# SH1-POWER.net
KiCad netlist of a schematic drawn in Altium Designer
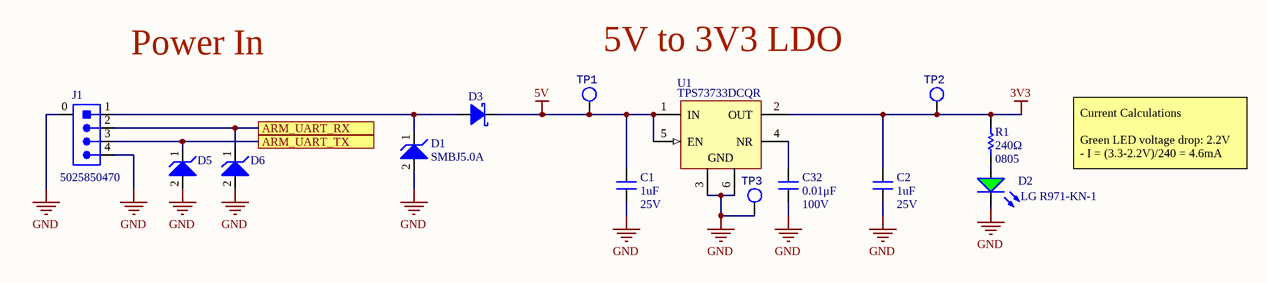
[diagram p0: SH1-POWER.SchDoc]

(export (version "E")
  (design (tool "Eeschema 10.0.6"))
  (components
    (comp (ref "C1")
      (value "~")
      (footprint "CAPC2012X140N")
      (description "CAP CER 1UF 25V X7R 0805")
      (fields
        (field (name "TOLERANCE") "10%")
        (field (name "CAPACITANCE") "1uF")
        (field (name "VOLTAGE RATING (DC)") "25V")
      )
      (libsource (lib "*") (part "CAP_1uF_25V_0805"))
    )
    (comp (ref "C2")
      (value "~")
      (footprint "CAPC2012X140N")
      (description "CAP CER 1UF 25V X7R 0805")
      (fields
        (field (name "TOLERANCE") "10%")
        (field (name "CAPACITANCE") "1uF")
        (field (name "VOLTAGE RATING (DC)") "25V")
      )
      (libsource (lib "*") (part "CAP_1uF_25V_0805"))
    )
    (comp (ref "C32")
      (value "0.01μF")
      (footprint "CAP2012")
      (description "CAP CER 10000PF 100V X7R 0805")
      (fields
        (field (name "TOLERANCE") "10%")
        (field (name "VOLTAGE RATING") "100V")
        (field (name "Comment") "CAP_0.01uF_100V_0805")
      )
      (libsource (lib "UWRT_Schematic_Library_2020") (part "CAP_0.01uF_100V_0805"))
    )
    (comp (ref "D1")
      (value "TVS_DIODE_UNIDIR_5V")
      (footprint "SMBJ5.0A")
      (description "TVS DIODE 5V 9.2V DO214AA")
      (fields (field (name "MANUFACTURER PART NUMBER 1") "SMBJ5.0A"))
      (libsource (lib "UWRT_Schematic_Library_2020") (part "TVS_DIODE_UNIDIR_5V"))
    )
    (comp (ref "D2")
      (value "LG R971-KN-1")
      (footprint "LED_0805_LINE")
      (description "LED GREEN DIFFUSED 0805 SMD")
      (libsource (lib "UWRT_Schematic_Library_2020") (part "DIO_LED_G"))
    )
    (comp (ref "D3")
      (value "DIO_SCHOTTKY_30V_2A")
      (footprint "SOD-128")
      (description "DIODE SCHOTTKY 30V 2A PMDTM")
      (libsource (lib "UWRT_Schematic_Library_2020") (part "DIO_SCHOTTKY_30V_2A"))
    )
    (comp (ref "D5")
      (value "TVS_DIODE_UNIDIR_3.3V")
      (footprint "SOD523")
      (description "TVS DIODE 3.3V 14.1V SOD523. Used to protect each connector input line going into the MCU.")
      (libsource (lib "UWRT_Schematic_Library_2020") (part "TVS_DIODE_UNIDIR_3.3V"))
    )
    (comp (ref "D6")
      (value "TVS_DIODE_UNIDIR_3.3V")
      (footprint "SOD523")
      (description "TVS DIODE 3.3V 14.1V SOD523. Used to protect each connector input line going into the MCU.")
      (libsource (lib "UWRT_Schematic_Library_2020") (part "TVS_DIODE_UNIDIR_3.3V"))
    )
    (comp (ref "J1")
      (value "CON_4M_SM_RA")
      (footprint "MOLEX-5025850470")
      (description "CONN HEADER SMD RIGHT ANGLE 1.5 MM PITCH")
      (fields (field (name "MANUFACTURER") "Molex") (field (name "MANUFACTOR NUMBER") "5025850470"))
      (libsource (lib "UWRT_Schematic_Library_2020") (part "CON_4M_SM_RA"))
    )
    (comp (ref "R1")
      (value "240")
      (footprint "RESC2012X60N")
      (description "RES 240 OHM 1% 1/8W 0805")
      (fields
        (field (name "TOLERANCE") "1%")
        (field (name "RESISTANCE") "240Ω")
        (field (name "CASE CODE (IMPERIAL)") "0805")
      )
      (libsource (lib "UWRT_Schematic_Library_2020") (part "RES_240Ω_0805_1%"))
    )
    (comp (ref "TP1")
      (value "TESTPOINT_LOOP")
      (footprint "TESTPOINT_LOOP")
      (description "Loop testpoint through-hole pad")
      (libsource (lib "UWRT_Schematic_Library_2020") (part "TESTPOINT_LOOP"))
    )
    (comp (ref "TP2")
      (value "TESTPOINT_LOOP")
      (footprint "TESTPOINT_LOOP")
      (description "Loop testpoint through-hole pad")
      (libsource (lib "UWRT_Schematic_Library_2020") (part "TESTPOINT_LOOP"))
    )
    (comp (ref "TP3")
      (value "TESTPOINT_LOOP")
      (footprint "TESTPOINT_LOOP")
      (description "Loop testpoint through-hole pad")
      (libsource (lib "UWRT_Schematic_Library_2020") (part "TESTPOINT_LOOP"))
    )
    (comp (ref "U1")
      (value "TPS73733DCQR")
      (footprint "UWRT_Footprint_Library_2020:SOT-223-6")
      (description "IC REG LINEAR 3.3V 1A SOT223-6")
      (fields (field (name "MANUFACTURER") "Texas Instruments"))
      (libsource (lib "Altium Content Vault") (part "LDO_3.3V_1A"))
    )
  )
  (nets
    (net (code "1") (name "/ARM_UART_RX") (class "Default")
      (node (ref "D6") (pin "1") (pinfunction "1_1") (pintype "passive"))
      (node (ref "J1") (pin "2") (pinfunction "2_2") (pintype "passive"))
    )
    (net (code "2") (name "/ARM_UART_TX") (class "Default")
      (node (ref "D5") (pin "1") (pinfunction "1_1") (pintype "passive"))
      (node (ref "J1") (pin "3") (pinfunction "3_3") (pintype "passive"))
    )
    (net (code "3") (name "3V3") (class "Default")
      (node (ref "C2") (pin "2") (pinfunction "2_2") (pintype "passive"))
      (node (ref "R1") (pin "2") (pinfunction "2_2") (pintype "passive"))
      (node (ref "TP2") (pin "1") (pintype "passive"))
      (node (ref "U1") (pin "2") (pinfunction "OUT_2") (pintype "power_in"))
    )
    (net (code "4") (name "5V") (class "Default")
      (node (ref "C1") (pin "1") (pinfunction "1_1") (pintype "passive"))
      (node (ref "D3") (pin "2") (pinfunction "Cathode_2") (pintype "passive"))
      (node (ref "TP1") (pin "1") (pintype "passive"))
      (node (ref "U1") (pin "1") (pinfunction "IN_1") (pintype "power_in"))
      (node (ref "U1") (pin "5") (pinfunction "EN_5") (pintype "input"))
    )
    (net (code "5") (name "GND") (class "Default")
      (node (ref "C1") (pin "2") (pinfunction "2_2") (pintype "passive"))
      (node (ref "C2") (pin "1") (pinfunction "1_1") (pintype "passive"))
      (node (ref "C32") (pin "1") (pinfunction "1_1") (pintype "passive"))
      (node (ref "D1") (pin "2") (pinfunction "2_2") (pintype "passive"))
      (node (ref "D2") (pin "2") (pinfunction "K_2") (pintype "passive"))
      (node (ref "D5") (pin "2") (pinfunction "2_2") (pintype "passive"))
      (node (ref "D6") (pin "2") (pinfunction "2_2") (pintype "passive"))
      (node (ref "J1") (pin "0") (pinfunction "0_0") (pintype "passive"))
      (node (ref "J1") (pin "4") (pinfunction "4_4") (pintype "passive"))
      (node (ref "TP3") (pin "1") (pintype "passive"))
      (node (ref "U1") (pin "3") (pinfunction "GND_3") (pintype "power_in"))
      (node (ref "U1") (pin "6") (pinfunction "GND_6") (pintype "power_in"))
    )
    (net (code "6") (name "Net-(D2-A)") (class "Default")
      (node (ref "D2") (pin "1") (pinfunction "A_1") (pintype "passive"))
      (node (ref "R1") (pin "1") (pinfunction "1_1") (pintype "passive"))
    )
    (net (code "7") (name "Net-(D3-Anode)") (class "Default")
      (node (ref "D1") (pin "1") (pinfunction "1_1") (pintype "passive"))
      (node (ref "D3") (pin "1") (pinfunction "Anode_1") (pintype "passive"))
      (node (ref "J1") (pin "1") (pinfunction "1_1") (pintype "passive"))
    )
    (net (code "8") (name "Net-(U1-NR)") (class "Default")
      (node (ref "C32") (pin "2") (pinfunction "2_2") (pintype "passive"))
      (node (ref "U1") (pin "4") (pinfunction "NR_4") (pintype "passive"))
    )
  )
)
